# WaveAnalysisBoard.net
KiCad netlist of a schematic drawn in EAGLE
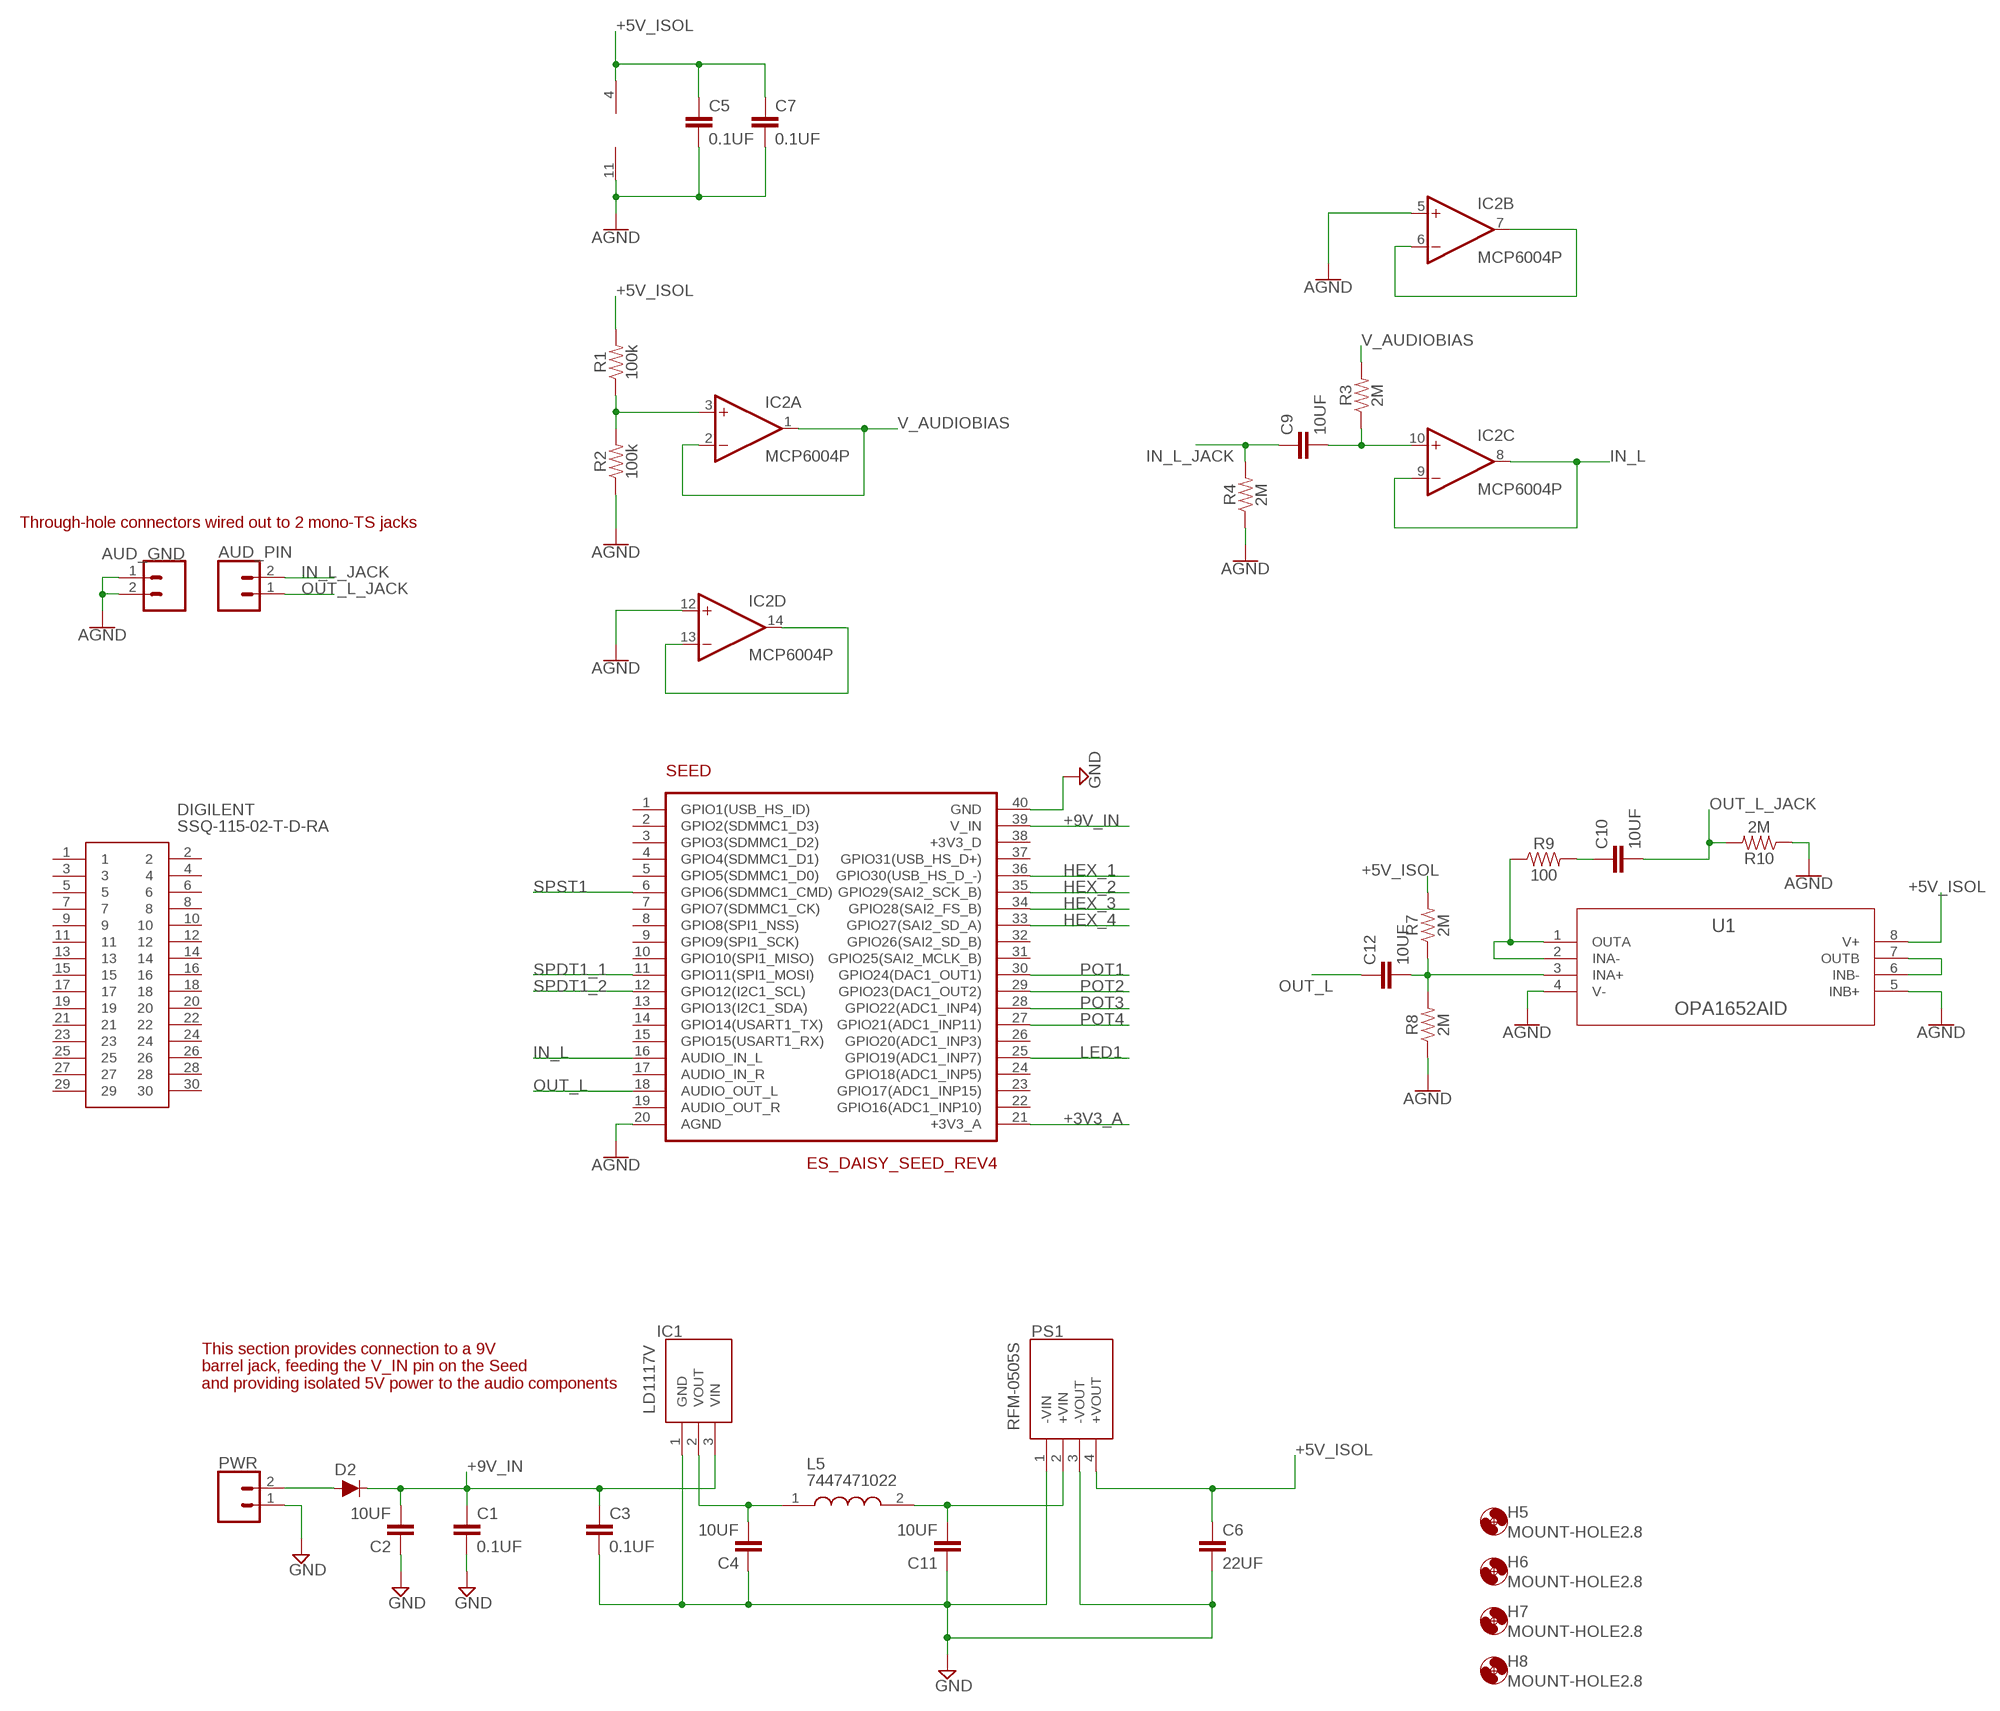
[diagram p0: schematic, sheet 1]
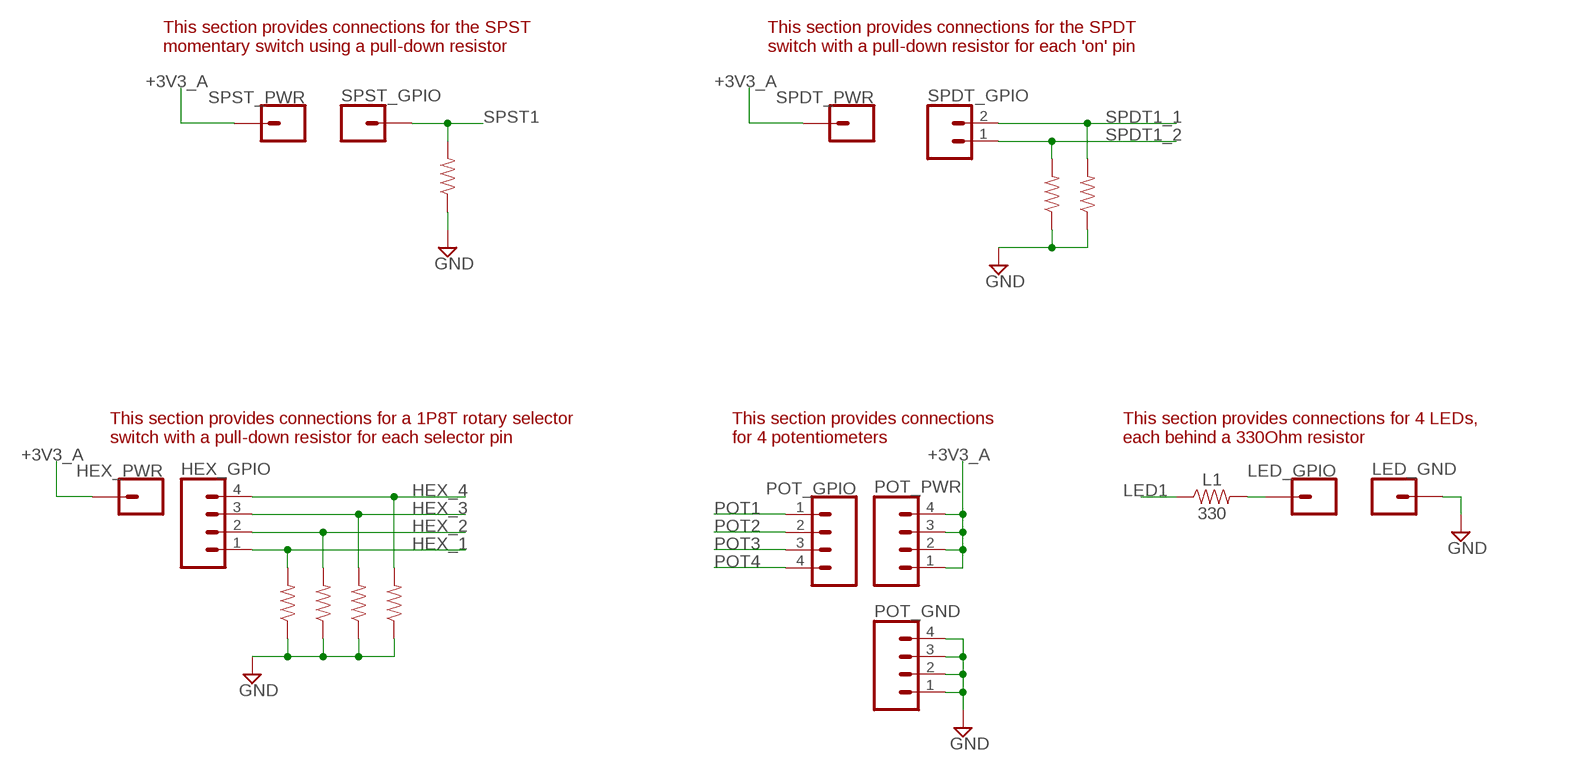
[diagram p1: schematic, sheet 2]

(export (version "E")
  (design (tool "Eeschema 10.0.6"))
  (components
    (comp (ref "AUD_GND")
      (value "CONN_02")
      (footprint "eagle-import:1X02")
      (libsource (lib "eagle-import") (part "CONN_02"))
    )
    (comp (ref "AUD_PIN")
      (value "CONN_02")
      (footprint "eagle-import:1X02")
      (libsource (lib "eagle-import") (part "CONN_02"))
    )
    (comp (ref "C1")
      (value "0.1UF")
      (footprint "eagle-import:CAP-PTH-SMALL-KIT")
      (libsource (lib "eagle-import") (part "0.1UF"))
    )
    (comp (ref "C2")
      (value "10UF")
      (footprint "eagle-import:CAP-PTH-SMALL-KIT")
      (libsource (lib "eagle-import") (part "10UF"))
    )
    (comp (ref "C3")
      (value "0.1UF")
      (footprint "eagle-import:CAP-PTH-SMALL-KIT")
      (libsource (lib "eagle-import") (part "0.1UF"))
    )
    (comp (ref "C4")
      (value "10UF")
      (footprint "eagle-import:CAP-PTH-SMALL-KIT")
      (libsource (lib "eagle-import") (part "10UF"))
    )
    (comp (ref "C5")
      (value "0.1UF")
      (footprint "eagle-import:CAP-PTH-SMALL-KIT")
      (libsource (lib "eagle-import") (part "0.1UF"))
    )
    (comp (ref "C6")
      (value "22UF")
      (footprint "eagle-import:CAP-PTH-SMALL-KIT")
      (libsource (lib "eagle-import") (part "22UF"))
    )
    (comp (ref "C7")
      (value "0.1UF")
      (footprint "eagle-import:CAP-PTH-SMALL-KIT")
      (libsource (lib "eagle-import") (part "0.1UF"))
    )
    (comp (ref "C9")
      (value "10UF")
      (footprint "eagle-import:CAP-PTH-SMALL-KIT")
      (libsource (lib "eagle-import") (part "10UF"))
    )
    (comp (ref "C10")
      (value "10UF")
      (footprint "eagle-import:CAP-PTH-SMALL-KIT")
      (libsource (lib "eagle-import") (part "10UF"))
    )
    (comp (ref "C11")
      (value "10UF")
      (footprint "eagle-import:CAP-PTH-SMALL-KIT")
      (libsource (lib "eagle-import") (part "10UF"))
    )
    (comp (ref "C12")
      (value "10UF")
      (footprint "eagle-import:CAP-PTH-SMALL-KIT")
      (libsource (lib "eagle-import") (part "10UF"))
    )
    (comp (ref "D2")
      (value "200mA/100V/1V")
      (footprint "eagle-import:DIODE-1N4148")
      (libsource (lib "eagle-import") (part "DIODE-1N4148"))
    )
    (comp (ref "DIGILENT")
      (value "SSQ-115-02-T-D-RA")
      (footprint "eagle-import:RHDRRA30W64P254_2X15_3861X851X")
      (fields (field (name "MOUSER_PART_NUMBER") "200-SSQ11502TDRA"))
      (libsource (lib "eagle-import") (part "SSQ-115-02-T-D-RA"))
    )
    (comp (ref "H5")
      (value "MOUNT-HOLE2.8")
      (footprint "eagle-import:2,8")
      (libsource (lib "eagle-import") (part "MOUNT-HOLE2.8"))
    )
    (comp (ref "H6")
      (value "MOUNT-HOLE2.8")
      (footprint "eagle-import:2,8")
      (libsource (lib "eagle-import") (part "MOUNT-HOLE2.8"))
    )
    (comp (ref "H7")
      (value "MOUNT-HOLE2.8")
      (footprint "eagle-import:2,8")
      (libsource (lib "eagle-import") (part "MOUNT-HOLE2.8"))
    )
    (comp (ref "H8")
      (value "MOUNT-HOLE2.8")
      (footprint "eagle-import:2,8")
      (libsource (lib "eagle-import") (part "MOUNT-HOLE2.8"))
    )
    (comp (ref "IC1")
      (value "LD1117V")
      (footprint "eagle-import:TO255P460X1020X2008-3P")
      (fields (field (name "MOUSER_PART_NUMBER") "511-LD1117V"))
      (libsource (lib "eagle-import") (part "LD1117V"))
    )
    (comp (ref "IC2")
      (value "MCP6004P")
      (footprint "eagle-import:DIL14")
      (libsource (lib "eagle-import") (part "MCP6004P"))
    )
    (comp (ref "L5")
      (value "7447471022")
      (footprint "eagle-import:WE-TIS_111190")
      (fields (field (name "MOUSER_PART_NUMBER") "710-7447471022"))
      (libsource (lib "eagle-import") (part "7447471022"))
    )
    (comp (ref "PS1")
      (value "RFM-0505S")
      (footprint "eagle-import:RFM0505S")
      (fields (field (name "MOUSER_PART_NUMBER") "919-RFM-0505S"))
      (libsource (lib "eagle-import") (part "RFM-0505S"))
    )
    (comp (ref "PWR")
      (value "CONN_02")
      (footprint "eagle-import:1X02")
      (libsource (lib "eagle-import") (part "CONN_02"))
    )
    (comp (ref "R1")
      (value "100k")
      (footprint "eagle-import:AXIAL-0.3")
      (libsource (lib "eagle-import") (part "100KOHM-HORIZ-1/4W-5%"))
    )
    (comp (ref "R2")
      (value "100k")
      (footprint "eagle-import:AXIAL-0.3")
      (libsource (lib "eagle-import") (part "100KOHM-HORIZ-1/4W-5%"))
    )
    (comp (ref "R3")
      (value "2M")
      (footprint "eagle-import:AXIAL-0.3")
      (libsource (lib "eagle-import") (part "2MOHM-HORIZ-1/4W-5%"))
    )
    (comp (ref "R4")
      (value "2M")
      (footprint "eagle-import:AXIAL-0.3")
      (libsource (lib "eagle-import") (part "2MOHM-HORIZ-1/4W-5%"))
    )
    (comp (ref "R7")
      (value "2M")
      (footprint "eagle-import:AXIAL-0.3")
      (libsource (lib "eagle-import") (part "2MOHM-HORIZ-1/4W-5%"))
    )
    (comp (ref "R8")
      (value "2M")
      (footprint "eagle-import:AXIAL-0.3")
      (libsource (lib "eagle-import") (part "2MOHM-HORIZ-1/4W-5%"))
    )
    (comp (ref "R9")
      (value "100")
      (footprint "eagle-import:AXIAL-0.3")
      (libsource (lib "eagle-import") (part "100OHM-HORIZ-1/4W-1%"))
    )
    (comp (ref "R10")
      (value "2M")
      (footprint "eagle-import:AXIAL-0.3")
      (libsource (lib "eagle-import") (part "2MOHM-HORIZ-1/4W-5%"))
    )
    (comp (ref "SEED")
      (value "ES_DAISY_SEED_REV4")
      (footprint "eagle-import:ES_DAISY_SEED")
      (libsource (lib "eagle-import") (part "ES_DAISY_SEED_REV4"))
    )
    (comp (ref "U1")
      (value "OPA1652AID")
      (footprint "eagle-import:D8")
      (fields
        (field (name "GENERIC_PART_NUMBER") "OPA1652")
        (field (name "MANUFACTURER") "Texas Instruments")
      )
      (libsource (lib "eagle-import") (part "OPA1652AID"))
    )
    (comp (ref "D11")
      (value "10k")
      (footprint "eagle-import:AXIAL-0.3")
      (libsource (lib "eagle-import") (part "10KOHM-HORIZ-1/4W-5%"))
    )
    (comp (ref "D12")
      (value "10k")
      (footprint "eagle-import:AXIAL-0.3")
      (libsource (lib "eagle-import") (part "10KOHM-HORIZ-1/4W-5%"))
    )
    (comp (ref "H1")
      (value "10k")
      (footprint "eagle-import:AXIAL-0.3")
      (libsource (lib "eagle-import") (part "10KOHM-HORIZ-1/4W-5%"))
    )
    (comp (ref "H2")
      (value "10k")
      (footprint "eagle-import:AXIAL-0.3")
      (libsource (lib "eagle-import") (part "10KOHM-HORIZ-1/4W-5%"))
    )
    (comp (ref "H3")
      (value "10k")
      (footprint "eagle-import:AXIAL-0.3")
      (libsource (lib "eagle-import") (part "10KOHM-HORIZ-1/4W-5%"))
    )
    (comp (ref "H4")
      (value "10k")
      (footprint "eagle-import:AXIAL-0.3")
      (libsource (lib "eagle-import") (part "10KOHM-HORIZ-1/4W-5%"))
    )
    (comp (ref "HEX_GPIO")
      (value "CONN_04")
      (footprint "eagle-import:1X04")
      (libsource (lib "eagle-import") (part "CONN_04"))
    )
    (comp (ref "HEX_PWR")
      (value "CONN_01")
      (footprint "eagle-import:1X01")
      (libsource (lib "eagle-import") (part "CONN_01"))
    )
    (comp (ref "L1")
      (value "330")
      (footprint "eagle-import:AXIAL-0.3")
      (libsource (lib "eagle-import") (part "330OHM-HORIZ-1/10W-5%"))
    )
    (comp (ref "LED_GND")
      (value "CONN_01")
      (footprint "eagle-import:1X01")
      (libsource (lib "eagle-import") (part "CONN_01"))
    )
    (comp (ref "LED_GPIO")
      (value "CONN_01")
      (footprint "eagle-import:1X01")
      (libsource (lib "eagle-import") (part "CONN_01"))
    )
    (comp (ref "POT_GND")
      (value "CONN_04")
      (footprint "eagle-import:1X04")
      (libsource (lib "eagle-import") (part "CONN_04"))
    )
    (comp (ref "POT_GPIO")
      (value "CONN_04")
      (footprint "eagle-import:1X04")
      (libsource (lib "eagle-import") (part "CONN_04"))
    )
    (comp (ref "POT_PWR")
      (value "CONN_04")
      (footprint "eagle-import:1X04")
      (libsource (lib "eagle-import") (part "CONN_04"))
    )
    (comp (ref "S1")
      (value "10k")
      (footprint "eagle-import:AXIAL-0.3")
      (libsource (lib "eagle-import") (part "10KOHM-HORIZ-1/4W-5%"))
    )
    (comp (ref "SPDT_GPIO")
      (value "CONN_02")
      (footprint "eagle-import:1X02")
      (libsource (lib "eagle-import") (part "CONN_02"))
    )
    (comp (ref "SPDT_PWR")
      (value "CONN_01")
      (footprint "eagle-import:1X01")
      (libsource (lib "eagle-import") (part "CONN_01"))
    )
    (comp (ref "SPST_GPIO")
      (value "CONN_01")
      (footprint "eagle-import:1X01")
      (libsource (lib "eagle-import") (part "CONN_01"))
    )
    (comp (ref "SPST_PWR")
      (value "CONN_01")
      (footprint "eagle-import:1X01")
      (libsource (lib "eagle-import") (part "CONN_01"))
    )
  )
  (nets
    (net (code "1") (name "+3V3_A") (class "Default")
      (node (ref "HEX_PWR") (pin "1") (pinfunction "1_1") (pintype "passive"))
      (node (ref "POT_PWR") (pin "1") (pinfunction "1_1") (pintype "passive"))
      (node (ref "POT_PWR") (pin "2") (pinfunction "2_2") (pintype "passive"))
      (node (ref "POT_PWR") (pin "3") (pinfunction "3_3") (pintype "passive"))
      (node (ref "POT_PWR") (pin "4") (pinfunction "4_4") (pintype "passive"))
      (node (ref "SEED") (pin "21") (pinfunction "+3V3_A_21") (pintype "bidirectional"))
      (node (ref "SPDT_PWR") (pin "1") (pinfunction "1_1") (pintype "passive"))
      (node (ref "SPST_PWR") (pin "1") (pinfunction "1_1") (pintype "passive"))
    )
    (net (code "2") (name "+5V_ISOL") (class "Default")
      (node (ref "C5") (pin "1") (pinfunction "1_1") (pintype "passive"))
      (node (ref "C6") (pin "1") (pinfunction "1_1") (pintype "passive"))
      (node (ref "C7") (pin "1") (pinfunction "1_1") (pintype "passive"))
      (node (ref "IC2") (pin "4") (pinfunction "V+_4") (pintype "power_in"))
      (node (ref "PS1") (pin "4") (pinfunction "+VOUT_4") (pintype "bidirectional"))
      (node (ref "R1") (pin "P$2") (pinfunction "2_P$2") (pintype "passive"))
      (node (ref "R7") (pin "P$2") (pinfunction "2_P$2") (pintype "passive"))
      (node (ref "U1") (pin "8") (pinfunction "V+_8") (pintype "power_in"))
    )
    (net (code "3") (name "+9V_IN") (class "Default")
      (node (ref "C1") (pin "1") (pinfunction "1_1") (pintype "passive"))
      (node (ref "C2") (pin "2") (pinfunction "2_2") (pintype "passive"))
      (node (ref "C3") (pin "1") (pinfunction "1_1") (pintype "passive"))
      (node (ref "D2") (pin "C") (pinfunction "C_C") (pintype "passive"))
      (node (ref "IC1") (pin "3") (pinfunction "VIN_3") (pintype "bidirectional"))
      (node (ref "SEED") (pin "39") (pinfunction "V_IN_39") (pintype "bidirectional"))
    )
    (net (code "4") (name "AGND") (class "Default")
      (node (ref "AUD_GND") (pin "1") (pinfunction "1_1") (pintype "passive"))
      (node (ref "AUD_GND") (pin "2") (pinfunction "2_2") (pintype "passive"))
      (node (ref "C5") (pin "2") (pinfunction "2_2") (pintype "passive"))
      (node (ref "C7") (pin "2") (pinfunction "2_2") (pintype "passive"))
      (node (ref "IC2") (pin "11") (pinfunction "V-_11") (pintype "power_in"))
      (node (ref "IC2") (pin "12") (pinfunction "+IN_12") (pintype "input"))
      (node (ref "IC2") (pin "5") (pinfunction "+IN_5") (pintype "input"))
      (node (ref "R10") (pin "P$1") (pinfunction "1_P$1") (pintype "passive"))
      (node (ref "R2") (pin "P$1") (pinfunction "1_P$1") (pintype "passive"))
      (node (ref "R4") (pin "P$1") (pinfunction "1_P$1") (pintype "passive"))
      (node (ref "R8") (pin "P$1") (pinfunction "1_P$1") (pintype "passive"))
      (node (ref "SEED") (pin "20") (pinfunction "AGND_20") (pintype "bidirectional"))
      (node (ref "U1") (pin "4") (pinfunction "V-_4") (pintype "power_in"))
      (node (ref "U1") (pin "5") (pinfunction "INB+_5") (pintype "input"))
    )
    (net (code "5") (name "GND") (class "Default")
      (node (ref "C1") (pin "2") (pinfunction "2_2") (pintype "passive"))
      (node (ref "C11") (pin "1") (pinfunction "1_1") (pintype "passive"))
      (node (ref "C2") (pin "1") (pinfunction "1_1") (pintype "passive"))
      (node (ref "C3") (pin "2") (pinfunction "2_2") (pintype "passive"))
      (node (ref "C4") (pin "1") (pinfunction "1_1") (pintype "passive"))
      (node (ref "C6") (pin "2") (pinfunction "2_2") (pintype "passive"))
      (node (ref "D11") (pin "P$1") (pinfunction "1_P$1") (pintype "passive"))
      (node (ref "D12") (pin "P$1") (pinfunction "1_P$1") (pintype "passive"))
      (node (ref "H1") (pin "P$1") (pinfunction "1_P$1") (pintype "passive"))
      (node (ref "H2") (pin "P$1") (pinfunction "1_P$1") (pintype "passive"))
      (node (ref "H3") (pin "P$1") (pinfunction "1_P$1") (pintype "passive"))
      (node (ref "H4") (pin "P$1") (pinfunction "1_P$1") (pintype "passive"))
      (node (ref "IC1") (pin "1") (pinfunction "GND_1") (pintype "bidirectional"))
      (node (ref "LED_GND") (pin "1") (pinfunction "1_1") (pintype "passive"))
      (node (ref "POT_GND") (pin "1") (pinfunction "1_1") (pintype "passive"))
      (node (ref "POT_GND") (pin "2") (pinfunction "2_2") (pintype "passive"))
      (node (ref "POT_GND") (pin "3") (pinfunction "3_3") (pintype "passive"))
      (node (ref "POT_GND") (pin "4") (pinfunction "4_4") (pintype "passive"))
      (node (ref "PS1") (pin "1") (pinfunction "-VIN_1") (pintype "bidirectional"))
      (node (ref "PS1") (pin "3") (pinfunction "-VOUT_3") (pintype "bidirectional"))
      (node (ref "PWR") (pin "1") (pinfunction "1_1") (pintype "passive"))
      (node (ref "S1") (pin "P$1") (pinfunction "1_P$1") (pintype "passive"))
      (node (ref "SEED") (pin "40") (pinfunction "GND_40") (pintype "bidirectional"))
    )
    (net (code "6") (name "HEX_1") (class "Default")
      (node (ref "H1") (pin "P$2") (pinfunction "2_P$2") (pintype "passive"))
      (node (ref "HEX_GPIO") (pin "1") (pinfunction "1_1") (pintype "passive"))
      (node (ref "SEED") (pin "36") (pinfunction "GPIO30(USB_HS_D_-)_36") (pintype "bidirectional"))
    )
    (net (code "7") (name "HEX_2") (class "Default")
      (node (ref "H2") (pin "P$2") (pinfunction "2_P$2") (pintype "passive"))
      (node (ref "HEX_GPIO") (pin "2") (pinfunction "2_2") (pintype "passive"))
      (node (ref "SEED") (pin "35") (pinfunction "GPIO29(SAI2_SCK_B)_35") (pintype "bidirectional"))
    )
    (net (code "8") (name "HEX_3") (class "Default")
      (node (ref "H3") (pin "P$2") (pinfunction "2_P$2") (pintype "passive"))
      (node (ref "HEX_GPIO") (pin "3") (pinfunction "3_3") (pintype "passive"))
      (node (ref "SEED") (pin "34") (pinfunction "GPIO28(SAI2_FS_B)_34") (pintype "bidirectional"))
    )
    (net (code "9") (name "HEX_4") (class "Default")
      (node (ref "H4") (pin "P$2") (pinfunction "2_P$2") (pintype "passive"))
      (node (ref "HEX_GPIO") (pin "4") (pinfunction "4_4") (pintype "passive"))
      (node (ref "SEED") (pin "33") (pinfunction "GPIO27(SAI2_SD_A)_33") (pintype "bidirectional"))
    )
    (net (code "10") (name "IN_L") (class "Default")
      (node (ref "IC2") (pin "8") (pinfunction "OUT_8") (pintype "output"))
      (node (ref "IC2") (pin "9") (pinfunction "-IN_9") (pintype "input"))
      (node (ref "SEED") (pin "16") (pinfunction "AUDIO_IN_L_16") (pintype "bidirectional"))
    )
    (net (code "11") (name "IN_L_JACK") (class "Default")
      (node (ref "AUD_PIN") (pin "2") (pinfunction "2_2") (pintype "passive"))
      (node (ref "C9") (pin "1") (pinfunction "1_1") (pintype "passive"))
      (node (ref "R4") (pin "P$2") (pinfunction "2_P$2") (pintype "passive"))
    )
    (net (code "12") (name "LED1") (class "Default")
      (node (ref "L1") (pin "P$1") (pinfunction "1_P$1") (pintype "passive"))
      (node (ref "SEED") (pin "25") (pinfunction "GPIO19(ADC1_INP7)_25") (pintype "bidirectional"))
    )
    (net (code "13") (name "Net-(D2-PadA)") (class "Default")
      (node (ref "D2") (pin "A") (pinfunction "A_A") (pintype "passive"))
      (node (ref "PWR") (pin "2") (pinfunction "2_2") (pintype "passive"))
    )
    (net (code "14") (name "Net-(IC1-VOUT)") (class "Default")
      (node (ref "C4") (pin "2") (pinfunction "2_2") (pintype "passive"))
      (node (ref "IC1") (pin "2") (pinfunction "VOUT_2") (pintype "bidirectional"))
      (node (ref "L5") (pin "1") (pinfunction "1_1") (pintype "bidirectional"))
    )
    (net (code "15") (name "Net-(IC2A-+IN)") (class "Default")
      (node (ref "IC2") (pin "3") (pinfunction "+IN_3") (pintype "input"))
      (node (ref "R1") (pin "P$1") (pinfunction "1_P$1") (pintype "passive"))
      (node (ref "R2") (pin "P$2") (pinfunction "2_P$2") (pintype "passive"))
    )
    (net (code "16") (name "Net-(IC2B--IN)") (class "Default")
      (node (ref "IC2") (pin "6") (pinfunction "-IN_6") (pintype "input"))
      (node (ref "IC2") (pin "7") (pinfunction "OUT_7") (pintype "output"))
    )
    (net (code "17") (name "Net-(IC2C-+IN)") (class "Default")
      (node (ref "C9") (pin "2") (pinfunction "2_2") (pintype "passive"))
      (node (ref "IC2") (pin "10") (pinfunction "+IN_10") (pintype "input"))
      (node (ref "R3") (pin "P$1") (pinfunction "1_P$1") (pintype "passive"))
    )
    (net (code "18") (name "Net-(IC2D--IN)") (class "Default")
      (node (ref "IC2") (pin "13") (pinfunction "-IN_13") (pintype "input"))
      (node (ref "IC2") (pin "14") (pinfunction "OUT_14") (pintype "output"))
    )
    (net (code "19") (name "Net-(L1-2)") (class "Default")
      (node (ref "L1") (pin "P$2") (pinfunction "2_P$2") (pintype "passive"))
      (node (ref "LED_GPIO") (pin "1") (pinfunction "1_1") (pintype "passive"))
    )
    (net (code "20") (name "Net-(PS1-+VIN)") (class "Default")
      (node (ref "C11") (pin "2") (pinfunction "2_2") (pintype "passive"))
      (node (ref "L5") (pin "2") (pinfunction "2_2") (pintype "bidirectional"))
      (node (ref "PS1") (pin "2") (pinfunction "+VIN_2") (pintype "bidirectional"))
    )
    (net (code "21") (name "Net-(R7-1)") (class "Default")
      (node (ref "C12") (pin "2") (pinfunction "2_2") (pintype "passive"))
      (node (ref "R7") (pin "P$1") (pinfunction "1_P$1") (pintype "passive"))
      (node (ref "R8") (pin "P$2") (pinfunction "2_P$2") (pintype "passive"))
      (node (ref "U1") (pin "3") (pinfunction "INA+_3") (pintype "input"))
    )
    (net (code "22") (name "Net-(R9-1)") (class "Default")
      (node (ref "R9") (pin "P$1") (pinfunction "1_P$1") (pintype "passive"))
      (node (ref "U1") (pin "1") (pinfunction "OUTA_1") (pintype "output"))
      (node (ref "U1") (pin "2") (pinfunction "INA-_2") (pintype "input"))
    )
    (net (code "23") (name "Net-(R9-2)") (class "Default")
      (node (ref "C10") (pin "1") (pinfunction "1_1") (pintype "passive"))
      (node (ref "R9") (pin "P$2") (pinfunction "2_P$2") (pintype "passive"))
    )
    (net (code "24") (name "Net-(U1-INB-)") (class "Default")
      (node (ref "U1") (pin "6") (pinfunction "INB-_6") (pintype "input"))
      (node (ref "U1") (pin "7") (pinfunction "OUTB_7") (pintype "output"))
    )
    (net (code "25") (name "OUT_L") (class "Default")
      (node (ref "C12") (pin "1") (pinfunction "1_1") (pintype "passive"))
      (node (ref "SEED") (pin "18") (pinfunction "AUDIO_OUT_L_18") (pintype "bidirectional"))
    )
    (net (code "26") (name "OUT_L_JACK") (class "Default")
      (node (ref "AUD_PIN") (pin "1") (pinfunction "1_1") (pintype "passive"))
      (node (ref "C10") (pin "2") (pinfunction "2_2") (pintype "passive"))
      (node (ref "R10") (pin "P$2") (pinfunction "2_P$2") (pintype "passive"))
    )
    (net (code "27") (name "POT1") (class "Default")
      (node (ref "POT_GPIO") (pin "1") (pinfunction "1_1") (pintype "passive"))
      (node (ref "SEED") (pin "30") (pinfunction "GPIO24(DAC1_OUT1)_30") (pintype "bidirectional"))
    )
    (net (code "28") (name "POT2") (class "Default")
      (node (ref "POT_GPIO") (pin "2") (pinfunction "2_2") (pintype "passive"))
      (node (ref "SEED") (pin "29") (pinfunction "GPIO23(DAC1_OUT2)_29") (pintype "bidirectional"))
    )
    (net (code "29") (name "POT3") (class "Default")
      (node (ref "POT_GPIO") (pin "3") (pinfunction "3_3") (pintype "passive"))
      (node (ref "SEED") (pin "28") (pinfunction "GPIO22(ADC1_INP4)_28") (pintype "bidirectional"))
    )
    (net (code "30") (name "POT4") (class "Default")
      (node (ref "POT_GPIO") (pin "4") (pinfunction "4_4") (pintype "passive"))
      (node (ref "SEED") (pin "27") (pinfunction "GPIO21(ADC1_INP11)_27") (pintype "bidirectional"))
    )
    (net (code "31") (name "SPDT1_1") (class "Default")
      (node (ref "D11") (pin "P$2") (pinfunction "2_P$2") (pintype "passive"))
      (node (ref "SEED") (pin "11") (pinfunction "GPIO11(SPI1_MOSI)_11") (pintype "bidirectional"))
      (node (ref "SPDT_GPIO") (pin "2") (pinfunction "2_2") (pintype "passive"))
    )
    (net (code "32") (name "SPDT1_2") (class "Default")
      (node (ref "D12") (pin "P$2") (pinfunction "2_P$2") (pintype "passive"))
      (node (ref "SEED") (pin "12") (pinfunction "GPIO12(I2C1_SCL)_12") (pintype "bidirectional"))
      (node (ref "SPDT_GPIO") (pin "1") (pinfunction "1_1") (pintype "passive"))
    )
    (net (code "33") (name "SPST1") (class "Default")
      (node (ref "S1") (pin "P$2") (pinfunction "2_P$2") (pintype "passive"))
      (node (ref "SEED") (pin "6") (pinfunction "GPIO6(SDMMC1_CMD)_6") (pintype "bidirectional"))
      (node (ref "SPST_GPIO") (pin "1") (pinfunction "1_1") (pintype "passive"))
    )
    (net (code "34") (name "V_AUDIOBIAS") (class "Default")
      (node (ref "IC2") (pin "1") (pinfunction "OUT_1") (pintype "output"))
      (node (ref "IC2") (pin "2") (pinfunction "-IN_2") (pintype "input"))
      (node (ref "R3") (pin "P$2") (pinfunction "2_P$2") (pintype "passive"))
    )
    (net (code "35") (name "unconnected-(DIGILENT-Pad1)") (class "Default")
      (node (ref "DIGILENT") (pin "1") (pinfunction "1_1") (pintype "bidirectional"))
    )
    (net (code "36") (name "unconnected-(DIGILENT-Pad2)") (class "Default")
      (node (ref "DIGILENT") (pin "2") (pinfunction "2_2") (pintype "bidirectional"))
    )
    (net (code "37") (name "unconnected-(DIGILENT-Pad3)") (class "Default")
      (node (ref "DIGILENT") (pin "3") (pinfunction "3_3") (pintype "bidirectional"))
    )
    (net (code "38") (name "unconnected-(DIGILENT-Pad4)") (class "Default")
      (node (ref "DIGILENT") (pin "4") (pinfunction "4_4") (pintype "bidirectional"))
    )
    (net (code "39") (name "unconnected-(DIGILENT-Pad5)") (class "Default")
      (node (ref "DIGILENT") (pin "5") (pinfunction "5_5") (pintype "bidirectional"))
    )
    (net (code "40") (name "unconnected-(DIGILENT-Pad6)") (class "Default")
      (node (ref "DIGILENT") (pin "6") (pinfunction "6_6") (pintype "bidirectional"))
    )
    (net (code "41") (name "unconnected-(DIGILENT-Pad7)") (class "Default")
      (node (ref "DIGILENT") (pin "7") (pinfunction "7_7") (pintype "bidirectional"))
    )
    (net (code "42") (name "unconnected-(DIGILENT-Pad8)") (class "Default")
      (node (ref "DIGILENT") (pin "8") (pinfunction "8_8") (pintype "bidirectional"))
    )
    (net (code "43") (name "unconnected-(DIGILENT-Pad9)") (class "Default")
      (node (ref "DIGILENT") (pin "9") (pinfunction "9_9") (pintype "bidirectional"))
    )
    (net (code "44") (name "unconnected-(DIGILENT-Pad10)") (class "Default")
      (node (ref "DIGILENT") (pin "10") (pinfunction "10_10") (pintype "bidirectional"))
    )
    (net (code "45") (name "unconnected-(DIGILENT-Pad11)") (class "Default")
      (node (ref "DIGILENT") (pin "11") (pinfunction "11_11") (pintype "bidirectional"))
    )
    (net (code "46") (name "unconnected-(DIGILENT-Pad12)") (class "Default")
      (node (ref "DIGILENT") (pin "12") (pinfunction "12_12") (pintype "bidirectional"))
    )
    (net (code "47") (name "unconnected-(DIGILENT-Pad13)") (class "Default")
      (node (ref "DIGILENT") (pin "13") (pinfunction "13_13") (pintype "bidirectional"))
    )
    (net (code "48") (name "unconnected-(DIGILENT-Pad14)") (class "Default")
      (node (ref "DIGILENT") (pin "14") (pinfunction "14_14") (pintype "bidirectional"))
    )
    (net (code "49") (name "unconnected-(DIGILENT-Pad15)") (class "Default")
      (node (ref "DIGILENT") (pin "15") (pinfunction "15_15") (pintype "bidirectional"))
    )
    (net (code "50") (name "unconnected-(DIGILENT-Pad16)") (class "Default")
      (node (ref "DIGILENT") (pin "16") (pinfunction "16_16") (pintype "bidirectional"))
    )
    (net (code "51") (name "unconnected-(DIGILENT-Pad17)") (class "Default")
      (node (ref "DIGILENT") (pin "17") (pinfunction "17_17") (pintype "bidirectional"))
    )
    (net (code "52") (name "unconnected-(DIGILENT-Pad18)") (class "Default")
      (node (ref "DIGILENT") (pin "18") (pinfunction "18_18") (pintype "bidirectional"))
    )
    (net (code "53") (name "unconnected-(DIGILENT-Pad19)") (class "Default")
      (node (ref "DIGILENT") (pin "19") (pinfunction "19_19") (pintype "bidirectional"))
    )
    (net (code "54") (name "unconnected-(DIGILENT-Pad20)") (class "Default")
      (node (ref "DIGILENT") (pin "20") (pinfunction "20_20") (pintype "bidirectional"))
    )
    (net (code "55") (name "unconnected-(DIGILENT-Pad21)") (class "Default")
      (node (ref "DIGILENT") (pin "21") (pinfunction "21_21") (pintype "bidirectional"))
    )
    (net (code "56") (name "unconnected-(DIGILENT-Pad22)") (class "Default")
      (node (ref "DIGILENT") (pin "22") (pinfunction "22_22") (pintype "bidirectional"))
    )
    (net (code "57") (name "unconnected-(DIGILENT-Pad23)") (class "Default")
      (node (ref "DIGILENT") (pin "23") (pinfunction "23_23") (pintype "bidirectional"))
    )
    (net (code "58") (name "unconnected-(DIGILENT-Pad24)") (class "Default")
      (node (ref "DIGILENT") (pin "24") (pinfunction "24_24") (pintype "bidirectional"))
    )
    (net (code "59") (name "unconnected-(DIGILENT-Pad25)") (class "Default")
      (node (ref "DIGILENT") (pin "25") (pinfunction "25_25") (pintype "bidirectional"))
    )
    (net (code "60") (name "unconnected-(DIGILENT-Pad26)") (class "Default")
      (node (ref "DIGILENT") (pin "26") (pinfunction "26_26") (pintype "bidirectional"))
    )
    (net (code "61") (name "unconnected-(DIGILENT-Pad27)") (class "Default")
      (node (ref "DIGILENT") (pin "27") (pinfunction "27_27") (pintype "bidirectional"))
    )
    (net (code "62") (name "unconnected-(DIGILENT-Pad28)") (class "Default")
      (node (ref "DIGILENT") (pin "28") (pinfunction "28_28") (pintype "bidirectional"))
    )
    (net (code "63") (name "unconnected-(DIGILENT-Pad29)") (class "Default")
      (node (ref "DIGILENT") (pin "29") (pinfunction "29_29") (pintype "bidirectional"))
    )
    (net (code "64") (name "unconnected-(DIGILENT-Pad30)") (class "Default")
      (node (ref "DIGILENT") (pin "30") (pinfunction "30_30") (pintype "bidirectional"))
    )
    (net (code "65") (name "unconnected-(SEED-+3V3_D-Pad38)") (class "Default")
      (node (ref "SEED") (pin "38") (pinfunction "+3V3_D_38") (pintype "bidirectional"))
    )
    (net (code "66") (name "unconnected-(SEED-AUDIO_IN_R-Pad17)") (class "Default")
      (node (ref "SEED") (pin "17") (pinfunction "AUDIO_IN_R_17") (pintype "bidirectional"))
    )
    (net (code "67") (name "unconnected-(SEED-AUDIO_OUT_R-Pad19)") (class "Default")
      (node (ref "SEED") (pin "19") (pinfunction "AUDIO_OUT_R_19") (pintype "bidirectional"))
    )
    (net (code "68") (name "unconnected-(SEED-GPIO1(USB_HS_ID)-Pad1)") (class "Default")
      (node (ref "SEED") (pin "1") (pinfunction "GPIO1(USB_HS_ID)_1") (pintype "bidirectional"))
    )
    (net (code "69") (name "unconnected-(SEED-GPIO2(SDMMC1_D3)-Pad2)") (class "Default")
      (node (ref "SEED") (pin "2") (pinfunction "GPIO2(SDMMC1_D3)_2") (pintype "bidirectional"))
    )
    (net (code "70") (name "unconnected-(SEED-GPIO3(SDMMC1_D2)-Pad3)") (class "Default")
      (node (ref "SEED") (pin "3") (pinfunction "GPIO3(SDMMC1_D2)_3") (pintype "bidirectional"))
    )
    (net (code "71") (name "unconnected-(SEED-GPIO4(SDMMC1_D1)-Pad4)") (class "Default")
      (node (ref "SEED") (pin "4") (pinfunction "GPIO4(SDMMC1_D1)_4") (pintype "bidirectional"))
    )
    (net (code "72") (name "unconnected-(SEED-GPIO5(SDMMC1_D0)-Pad5)") (class "Default")
      (node (ref "SEED") (pin "5") (pinfunction "GPIO5(SDMMC1_D0)_5") (pintype "bidirectional"))
    )
    (net (code "73") (name "unconnected-(SEED-GPIO7(SDMMC1_CK)-Pad7)") (class "Default")
      (node (ref "SEED") (pin "7") (pinfunction "GPIO7(SDMMC1_CK)_7") (pintype "bidirectional"))
    )
    (net (code "74") (name "unconnected-(SEED-GPIO8(SPI1_NSS)-Pad8)") (class "Default")
      (node (ref "SEED") (pin "8") (pinfunction "GPIO8(SPI1_NSS)_8") (pintype "bidirectional"))
    )
    (net (code "75") (name "unconnected-(SEED-GPIO9(SPI1_SCK)-Pad9)") (class "Default")
      (node (ref "SEED") (pin "9") (pinfunction "GPIO9(SPI1_SCK)_9") (pintype "bidirectional"))
    )
    (net (code "76") (name "unconnected-(SEED-GPIO10(SPI1_MISO)-Pad10)") (class "Default")
      (node (ref "SEED") (pin "10") (pinfunction "GPIO10(SPI1_MISO)_10") (pintype "bidirectional"))
    )
    (net (code "77") (name "unconnected-(SEED-GPIO13(I2C1_SDA)-Pad13)") (class "Default")
      (node (ref "SEED") (pin "13") (pinfunction "GPIO13(I2C1_SDA)_13") (pintype "bidirectional"))
    )
    (net (code "78") (name "unconnected-(SEED-GPIO14(USART1_TX)-Pad14)") (class "Default")
      (node (ref "SEED") (pin "14") (pinfunction "GPIO14(USART1_TX)_14") (pintype "bidirectional"))
    )
    (net (code "79") (name "unconnected-(SEED-GPIO15(USART1_RX)-Pad15)") (class "Default")
      (node (ref "SEED") (pin "15") (pinfunction "GPIO15(USART1_RX)_15") (pintype "bidirectional"))
    )
    (net (code "80") (name "unconnected-(SEED-GPIO16(ADC1_INP10)-Pad22)") (class "Default")
      (node (ref "SEED") (pin "22") (pinfunction "GPIO16(ADC1_INP10)_22") (pintype "bidirectional"))
    )
    (net (code "81") (name "unconnected-(SEED-GPIO17(ADC1_INP15)-Pad23)") (class "Default")
      (node (ref "SEED") (pin "23") (pinfunction "GPIO17(ADC1_INP15)_23") (pintype "bidirectional"))
    )
    (net (code "82") (name "unconnected-(SEED-GPIO18(ADC1_INP5)-Pad24)") (class "Default")
      (node (ref "SEED") (pin "24") (pinfunction "GPIO18(ADC1_INP5)_24") (pintype "bidirectional"))
    )
    (net (code "83") (name "unconnected-(SEED-GPIO20(ADC1_INP3)-Pad26)") (class "Default")
      (node (ref "SEED") (pin "26") (pinfunction "GPIO20(ADC1_INP3)_26") (pintype "bidirectional"))
    )
    (net (code "84") (name "unconnected-(SEED-GPIO25(SAI2_MCLK_B)-Pad31)") (class "Default")
      (node (ref "SEED") (pin "31") (pinfunction "GPIO25(SAI2_MCLK_B)_31") (pintype "bidirectional"))
    )
    (net (code "85") (name "unconnected-(SEED-GPIO26(SAI2_SD_B)-Pad32)") (class "Default")
      (node (ref "SEED") (pin "32") (pinfunction "GPIO26(SAI2_SD_B)_32") (pintype "bidirectional"))
    )
    (net (code "86") (name "unconnected-(SEED-GPIO31(USB_HS_D+)-Pad37)") (class "Default")
      (node (ref "SEED") (pin "37") (pinfunction "GPIO31(USB_HS_D+)_37") (pintype "bidirectional"))
    )
  )
)
